# Sheet1.net
KiCad netlist of a schematic drawn in Altium Designer
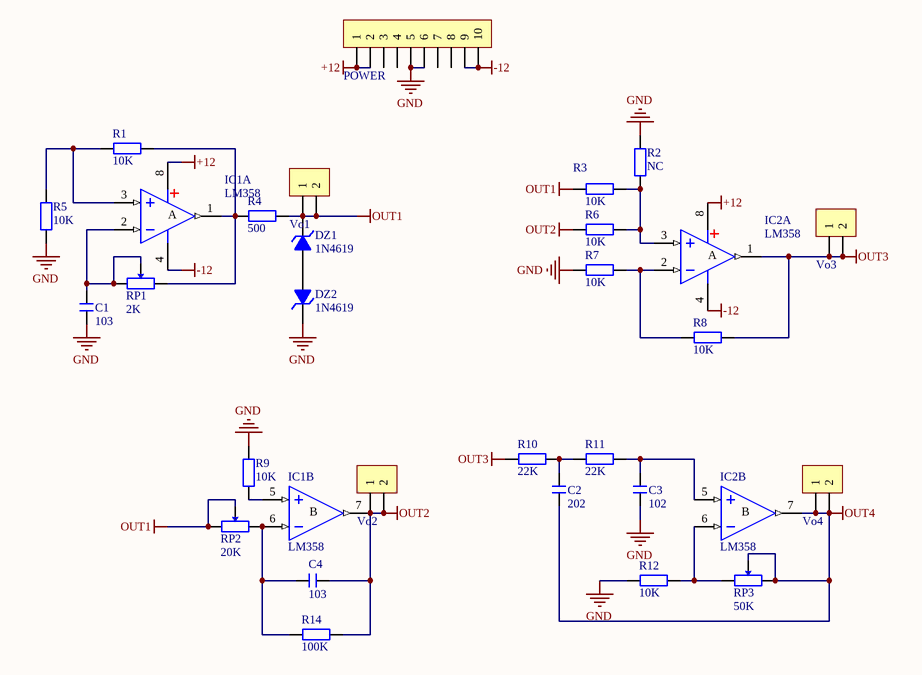
[diagram p0: Sheet1.SchDoc]

(export (version "E")
  (design (tool "Eeschema 10.0.6"))
  (components
    (comp (ref "C1")
      (value "103")
      (footprint "C 0805_L")
      (description "无极性贴片电容")
      (fields (field (name "版权归属") "源创客"))
      (libsource (lib "3.1   - 电阻-电容-电感") (part "C"))
    )
    (comp (ref "C2")
      (value "202")
      (footprint "C 0805_L")
      (description "无极性贴片电容")
      (fields (field (name "版权归属") "源创客"))
      (libsource (lib "3.1   - 电阻-电容-电感") (part "C"))
    )
    (comp (ref "C3")
      (value "102")
      (footprint "C 0805_L")
      (description "无极性贴片电容")
      (fields (field (name "版权归属") "源创客"))
      (libsource (lib "3.1   - 电阻-电容-电感") (part "C"))
    )
    (comp (ref "C4")
      (value "103")
      (footprint "C 0805_L")
      (description "无极性贴片电容")
      (fields (field (name "版权归属") "源创客"))
      (libsource (lib "3.1   - 电阻-电容-电感") (part "C"))
    )
    (comp (ref "DZ1")
      (value "1N4619")
      (footprint "DO-35")
      (description "3V/0.5W稳压管")
      (fields (field (name "版权归属") "源创客"))
      (libsource (lib "8.1   - 二极管-整流桥") (part "1N4619"))
    )
    (comp (ref "DZ2")
      (value "1N4619")
      (footprint "DO-35")
      (description "3V/0.5W稳压管")
      (fields (field (name "版权归属") "源创客"))
      (libsource (lib "8.1   - 二极管-整流桥") (part "1N4619"))
    )
    (comp (ref "IC1")
      (value "LM358")
      (footprint "SOP8_N")
      (description "双路运放")
      (fields (field (name "版权归属") "源创客"))
      (libsource (lib "1.1   - IC芯片") (part "LM358"))
    )
    (comp (ref "IC2")
      (value "LM358")
      (footprint "SOP8_N")
      (description "双路运放")
      (fields (field (name "版权归属") "源创客"))
      (libsource (lib "1.1   - IC芯片") (part "LM358"))
    )
    (comp (ref "POWER")
      (value "HDR-1X10")
      (footprint "HDR2.54-LI-10P")
      (description "10P接插件")
      (fields (field (name "版权归属") "源创客"))
      (libsource (lib "4.5   - 接插件-脚距2.54") (part "Header 10"))
    )
    (comp (ref "R1")
      (value "10K")
      (footprint "R 0805_L")
      (description "贴片电阻")
      (fields (field (name "版权归属") "源创客"))
      (libsource (lib "3.1   - 电阻-电容-电感") (part "R"))
    )
    (comp (ref "R2")
      (value "NC")
      (footprint "R 0805_L")
      (description "贴片电阻")
      (fields (field (name "版权归属") "源创客"))
      (libsource (lib "3.1   - 电阻-电容-电感") (part "R"))
    )
    (comp (ref "R3")
      (value "10K")
      (footprint "R 0805_L")
      (description "贴片电阻")
      (fields (field (name "版权归属") "源创客"))
      (libsource (lib "3.1   - 电阻-电容-电感") (part "R"))
    )
    (comp (ref "R4")
      (value "500")
      (footprint "R 0805_L")
      (description "贴片电阻")
      (fields (field (name "版权归属") "源创客"))
      (libsource (lib "3.1   - 电阻-电容-电感") (part "R"))
    )
    (comp (ref "R5")
      (value "10K")
      (footprint "R 0805_L")
      (description "贴片电阻")
      (fields (field (name "版权归属") "源创客"))
      (libsource (lib "3.1   - 电阻-电容-电感") (part "R"))
    )
    (comp (ref "R6")
      (value "10K")
      (footprint "R 0805_L")
      (description "贴片电阻")
      (fields (field (name "版权归属") "源创客"))
      (libsource (lib "3.1   - 电阻-电容-电感") (part "R"))
    )
    (comp (ref "R7")
      (value "10K")
      (footprint "R 0805_L")
      (description "贴片电阻")
      (fields (field (name "版权归属") "源创客"))
      (libsource (lib "3.1   - 电阻-电容-电感") (part "R"))
    )
    (comp (ref "R8")
      (value "10K")
      (footprint "R 0805_L")
      (description "贴片电阻")
      (fields (field (name "版权归属") "源创客"))
      (libsource (lib "3.1   - 电阻-电容-电感") (part "R"))
    )
    (comp (ref "R9")
      (value "10K")
      (footprint "R 0805_L")
      (description "贴片电阻")
      (fields (field (name "版权归属") "源创客"))
      (libsource (lib "3.1   - 电阻-电容-电感") (part "R"))
    )
    (comp (ref "R10")
      (value "22K")
      (footprint "R 0805_L")
      (description "贴片电阻")
      (fields (field (name "版权归属") "源创客"))
      (libsource (lib "3.1   - 电阻-电容-电感") (part "R"))
    )
    (comp (ref "R11")
      (value "22K")
      (footprint "R 0805_L")
      (description "贴片电阻")
      (fields (field (name "版权归属") "源创客"))
      (libsource (lib "3.1   - 电阻-电容-电感") (part "R"))
    )
    (comp (ref "R12")
      (value "10K")
      (footprint "R 0805_L")
      (description "贴片电阻")
      (fields (field (name "版权归属") "源创客"))
      (libsource (lib "3.1   - 电阻-电容-电感") (part "R"))
    )
    (comp (ref "R14")
      (value "100K")
      (footprint "R 0805_L")
      (description "贴片电阻")
      (fields (field (name "版权归属") "源创客"))
      (libsource (lib "3.1   - 电阻-电容-电感") (part "R"))
    )
    (comp (ref "RP1")
      (value "2K")
      (footprint "3296W")
      (description "插件单联电位器")
      (fields (field (name "版权归属") "源创客"))
      (libsource (lib "3.1   - 电阻-电容-电感") (part "RP-ID"))
    )
    (comp (ref "RP2")
      (value "20K")
      (footprint "3296W")
      (description "插件单联电位器")
      (fields (field (name "版权归属") "源创客"))
      (libsource (lib "3.1   - 电阻-电容-电感") (part "RP-ID"))
    )
    (comp (ref "RP3")
      (value "50K")
      (footprint "3296W")
      (description "插件单联电位器")
      (fields (field (name "版权归属") "源创客"))
      (libsource (lib "3.1   - 电阻-电容-电感") (part "RP-ID"))
    )
    (comp (ref "Vo1")
      (value "HDR-1X2")
      (footprint "HDR2.54-LI-2P")
      (description "2P接插件")
      (fields (field (name "版权归属") "源创客"))
      (libsource (lib "4.5   - 接插件-脚距2.54") (part "Header 2"))
    )
    (comp (ref "Vo2")
      (value "HDR-1X2")
      (footprint "HDR2.54-LI-2P")
      (description "2P接插件")
      (fields (field (name "版权归属") "源创客"))
      (libsource (lib "4.5   - 接插件-脚距2.54") (part "Header 2"))
    )
    (comp (ref "Vo3")
      (value "HDR-1X2")
      (footprint "HDR2.54-LI-2P")
      (description "2P接插件")
      (fields (field (name "版权归属") "源创客"))
      (libsource (lib "4.5   - 接插件-脚距2.54") (part "Header 2"))
    )
    (comp (ref "Vo4")
      (value "HDR-1X2")
      (footprint "HDR2.54-LI-2P")
      (description "2P接插件")
      (fields (field (name "版权归属") "源创客"))
      (libsource (lib "4.5   - 接插件-脚距2.54") (part "Header 2"))
    )
  )
  (nets
    (net (code "1") (name "+12") (class "Default")
      (node (ref "IC1") (pin "8") (pinfunction "V+_8") (pintype "power_in"))
      (node (ref "IC2") (pin "8") (pinfunction "V+_8") (pintype "power_in"))
      (node (ref "POWER") (pin "1") (pinfunction "1_1") (pintype "passive"))
      (node (ref "POWER") (pin "2") (pinfunction "2_2") (pintype "passive"))
    )
    (net (code "2") (name "-12") (class "Default")
      (node (ref "IC1") (pin "4") (pinfunction "V-_4") (pintype "power_in"))
      (node (ref "IC2") (pin "4") (pinfunction "V-_4") (pintype "power_in"))
      (node (ref "POWER") (pin "10") (pinfunction "10_10") (pintype "passive"))
      (node (ref "POWER") (pin "9") (pinfunction "9_9") (pintype "passive"))
    )
    (net (code "3") (name "GND") (class "Default")
      (node (ref "C1") (pin "1") (pinfunction "1_1") (pintype "passive"))
      (node (ref "C3") (pin "2") (pinfunction "2_2") (pintype "passive"))
      (node (ref "DZ2") (pin "2") (pinfunction "K_2") (pintype "passive"))
      (node (ref "POWER") (pin "5") (pinfunction "5_5") (pintype "passive"))
      (node (ref "POWER") (pin "6") (pinfunction "6_6") (pintype "passive"))
      (node (ref "R12") (pin "2") (pinfunction "2_2") (pintype "passive"))
      (node (ref "R2") (pin "1") (pinfunction "1_1") (pintype "passive"))
      (node (ref "R5") (pin "1") (pinfunction "1_1") (pintype "passive"))
      (node (ref "R7") (pin "2") (pinfunction "2_2") (pintype "passive"))
      (node (ref "R9") (pin "2") (pinfunction "2_2") (pintype "passive"))
    )
    (net (code "4") (name "Net-(C2-Pad1)") (class "Default")
      (node (ref "C2") (pin "1") (pinfunction "1_1") (pintype "passive"))
      (node (ref "R10") (pin "1") (pinfunction "1_1") (pintype "passive"))
      (node (ref "R11") (pin "2") (pinfunction "2_2") (pintype "passive"))
    )
    (net (code "5") (name "Net-(DZ1-A)") (class "Default")
      (node (ref "DZ1") (pin "1") (pinfunction "A_1") (pintype "passive"))
      (node (ref "DZ2") (pin "1") (pinfunction "A_1") (pintype "passive"))
    )
    (net (code "6") (name "Net-(IC1A-IN+)") (class "Default")
      (node (ref "IC1") (pin "3") (pinfunction "IN+_3") (pintype "input"))
      (node (ref "R1") (pin "2") (pinfunction "2_2") (pintype "passive"))
      (node (ref "R5") (pin "2") (pinfunction "2_2") (pintype "passive"))
    )
    (net (code "7") (name "Net-(IC1A-IN-)") (class "Default")
      (node (ref "C1") (pin "2") (pinfunction "2_2") (pintype "passive"))
      (node (ref "IC1") (pin "2") (pinfunction "IN-_2") (pintype "input"))
      (node (ref "RP1") (pin "1") (pinfunction "1_1") (pintype "passive"))
      (node (ref "RP1") (pin "2") (pinfunction "2_2") (pintype "passive"))
    )
    (net (code "8") (name "Net-(IC1A-OUT)") (class "Default")
      (node (ref "IC1") (pin "1") (pinfunction "OUT_1") (pintype "output"))
      (node (ref "R1") (pin "1") (pinfunction "1_1") (pintype "passive"))
      (node (ref "R4") (pin "2") (pinfunction "2_2") (pintype "passive"))
      (node (ref "RP1") (pin "3") (pinfunction "3_3") (pintype "passive"))
    )
    (net (code "9") (name "Net-(IC1B-IN+)") (class "Default")
      (node (ref "IC1") (pin "5") (pinfunction "IN+_5") (pintype "input"))
      (node (ref "R9") (pin "1") (pinfunction "1_1") (pintype "passive"))
    )
    (net (code "10") (name "Net-(IC1B-IN-)") (class "Default")
      (node (ref "C4") (pin "2") (pinfunction "2_2") (pintype "passive"))
      (node (ref "IC1") (pin "6") (pinfunction "IN-_6") (pintype "input"))
      (node (ref "R14") (pin "2") (pinfunction "2_2") (pintype "passive"))
      (node (ref "RP2") (pin "3") (pinfunction "3_3") (pintype "passive"))
    )
    (net (code "11") (name "Net-(IC2A-IN+)") (class "Default")
      (node (ref "IC2") (pin "3") (pinfunction "IN+_3") (pintype "input"))
      (node (ref "R2") (pin "2") (pinfunction "2_2") (pintype "passive"))
      (node (ref "R3") (pin "1") (pinfunction "1_1") (pintype "passive"))
      (node (ref "R6") (pin "1") (pinfunction "1_1") (pintype "passive"))
    )
    (net (code "12") (name "Net-(IC2A-IN-)") (class "Default")
      (node (ref "IC2") (pin "2") (pinfunction "IN-_2") (pintype "input"))
      (node (ref "R7") (pin "1") (pinfunction "1_1") (pintype "passive"))
      (node (ref "R8") (pin "2") (pinfunction "2_2") (pintype "passive"))
    )
    (net (code "13") (name "Net-(IC2B-IN+)") (class "Default")
      (node (ref "C3") (pin "1") (pinfunction "1_1") (pintype "passive"))
      (node (ref "IC2") (pin "5") (pinfunction "IN+_5") (pintype "input"))
      (node (ref "R11") (pin "1") (pinfunction "1_1") (pintype "passive"))
    )
    (net (code "14") (name "Net-(IC2B-IN-)") (class "Default")
      (node (ref "IC2") (pin "6") (pinfunction "IN-_6") (pintype "input"))
      (node (ref "R12") (pin "1") (pinfunction "1_1") (pintype "passive"))
      (node (ref "RP3") (pin "1") (pinfunction "1_1") (pintype "passive"))
    )
    (net (code "15") (name "OUT1") (class "Default")
      (node (ref "DZ1") (pin "2") (pinfunction "K_2") (pintype "passive"))
      (node (ref "R3") (pin "2") (pinfunction "2_2") (pintype "passive"))
      (node (ref "R4") (pin "1") (pinfunction "1_1") (pintype "passive"))
      (node (ref "RP2") (pin "1") (pinfunction "1_1") (pintype "passive"))
      (node (ref "RP2") (pin "2") (pinfunction "2_2") (pintype "passive"))
      (node (ref "Vo1") (pin "1") (pinfunction "1_1") (pintype "passive"))
      (node (ref "Vo1") (pin "2") (pinfunction "2_2") (pintype "passive"))
    )
    (net (code "16") (name "OUT2") (class "Default")
      (node (ref "C4") (pin "1") (pinfunction "1_1") (pintype "passive"))
      (node (ref "IC1") (pin "7") (pinfunction "OUT_7") (pintype "output"))
      (node (ref "R14") (pin "1") (pinfunction "1_1") (pintype "passive"))
      (node (ref "R6") (pin "2") (pinfunction "2_2") (pintype "passive"))
      (node (ref "Vo2") (pin "1") (pinfunction "1_1") (pintype "passive"))
      (node (ref "Vo2") (pin "2") (pinfunction "2_2") (pintype "passive"))
    )
    (net (code "17") (name "OUT3") (class "Default")
      (node (ref "IC2") (pin "1") (pinfunction "OUT_1") (pintype "output"))
      (node (ref "R10") (pin "2") (pinfunction "2_2") (pintype "passive"))
      (node (ref "R8") (pin "1") (pinfunction "1_1") (pintype "passive"))
      (node (ref "Vo3") (pin "1") (pinfunction "1_1") (pintype "passive"))
      (node (ref "Vo3") (pin "2") (pinfunction "2_2") (pintype "passive"))
    )
    (net (code "18") (name "OUT4") (class "Default")
      (node (ref "C2") (pin "2") (pinfunction "2_2") (pintype "passive"))
      (node (ref "IC2") (pin "7") (pinfunction "OUT_7") (pintype "output"))
      (node (ref "RP3") (pin "2") (pinfunction "2_2") (pintype "passive"))
      (node (ref "RP3") (pin "3") (pinfunction "3_3") (pintype "passive"))
      (node (ref "Vo4") (pin "1") (pinfunction "1_1") (pintype "passive"))
      (node (ref "Vo4") (pin "2") (pinfunction "2_2") (pintype "passive"))
    )
    (net (code "19") (name "unconnected-(POWER-Pad3)") (class "Default")
      (node (ref "POWER") (pin "3") (pinfunction "3_3") (pintype "passive"))
    )
    (net (code "20") (name "unconnected-(POWER-Pad4)") (class "Default")
      (node (ref "POWER") (pin "4") (pinfunction "4_4") (pintype "passive"))
    )
    (net (code "21") (name "unconnected-(POWER-Pad7)") (class "Default")
      (node (ref "POWER") (pin "7") (pinfunction "7_7") (pintype "passive"))
    )
    (net (code "22") (name "unconnected-(POWER-Pad8)") (class "Default")
      (node (ref "POWER") (pin "8") (pinfunction "8_8") (pintype "passive"))
    )
  )
)
